# AMini3350.net
KiCad netlist of a schematic drawn in EAGLE
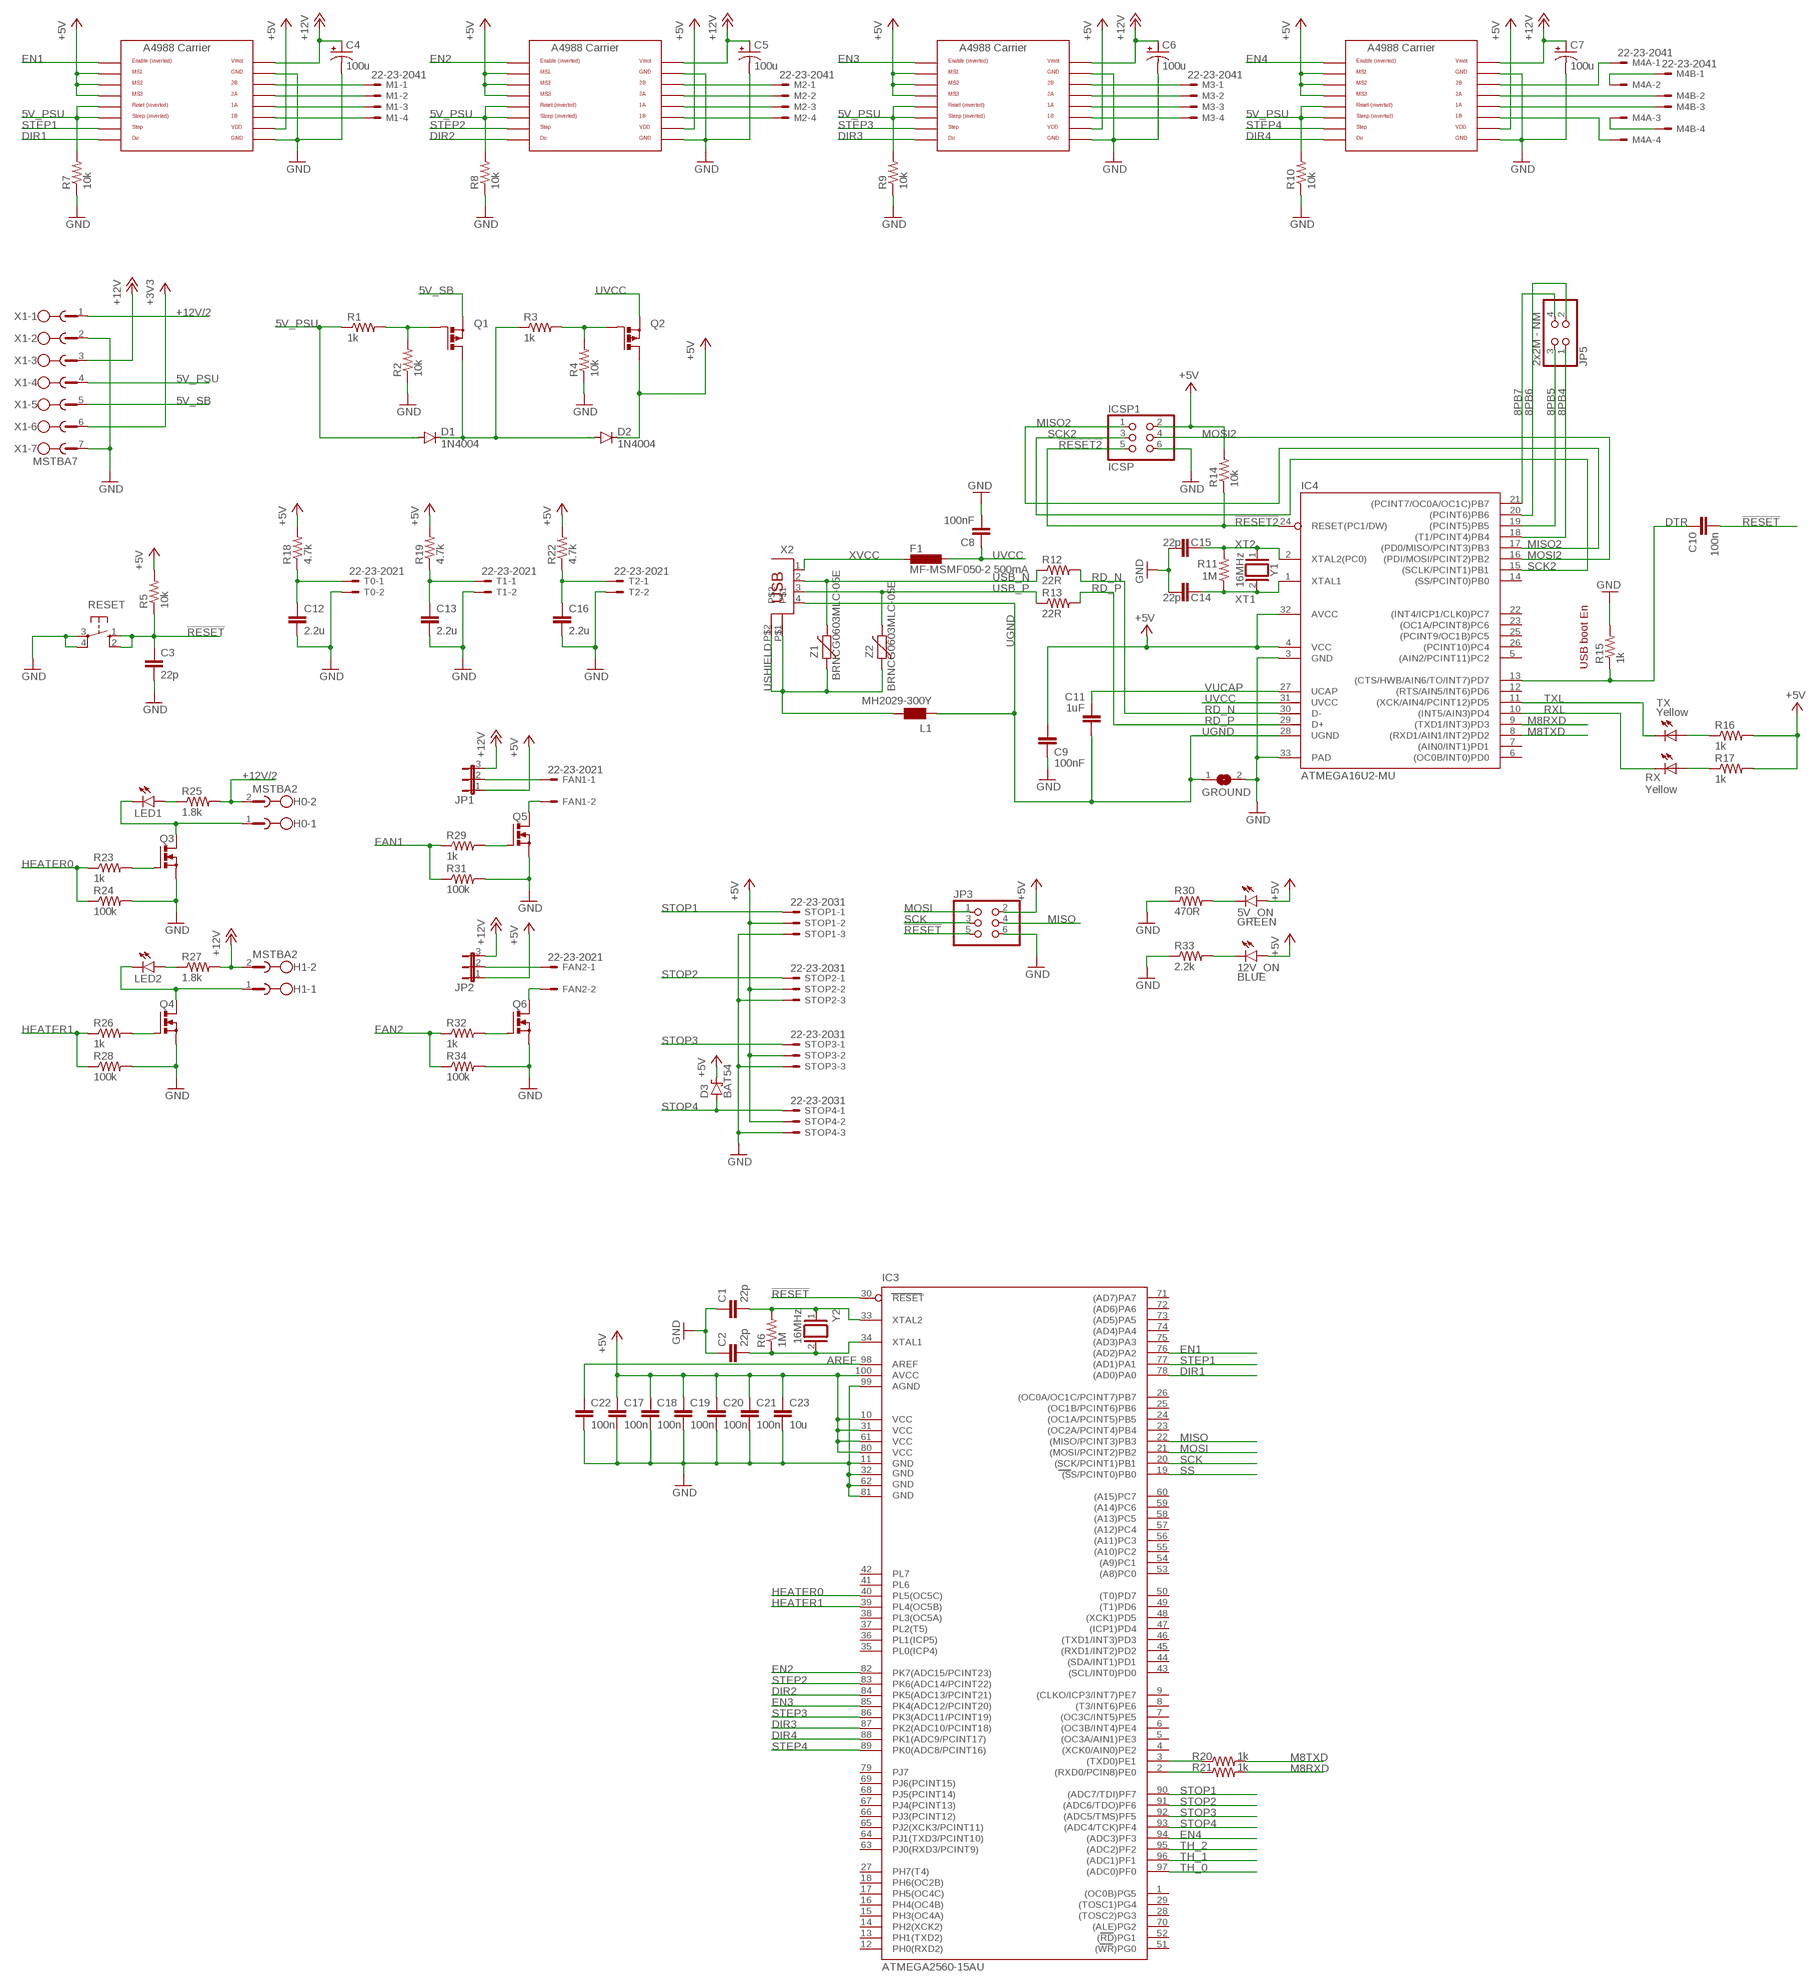
[diagram p0: schematic, sheet 1]

(export (version "E")
  (design (tool "Eeschema 10.0.6"))
  (components
    (comp (ref "5V_ON")
      (value "GREEN")
      (footprint "eagle-import:CHIP-LED0805")
      (libsource (lib "eagle-import") (part "LEDCHIP-LED0805"))
    )
    (comp (ref "12V_ON")
      (value "BLUE")
      (footprint "eagle-import:CHIP-LED0805")
      (libsource (lib "eagle-import") (part "LEDCHIP-LED0805"))
    )
    (comp (ref "C1")
      (value "22p")
      (footprint "eagle-import:C0603")
      (libsource (lib "eagle-import") (part "C-EUC0603"))
    )
    (comp (ref "C2")
      (value "22p")
      (footprint "eagle-import:C0603")
      (libsource (lib "eagle-import") (part "C-EUC0603"))
    )
    (comp (ref "C3")
      (value "22p")
      (footprint "eagle-import:C0603")
      (libsource (lib "eagle-import") (part "C-EUC0603"))
    )
    (comp (ref "C4")
      (value "100u")
      (footprint "eagle-import:PANASONIC_D")
      (libsource (lib "eagle-import") (part "CPOL-USD"))
    )
    (comp (ref "C5")
      (value "100u")
      (footprint "eagle-import:PANASONIC_D")
      (libsource (lib "eagle-import") (part "CPOL-USD"))
    )
    (comp (ref "C6")
      (value "100u")
      (footprint "eagle-import:PANASONIC_D")
      (libsource (lib "eagle-import") (part "CPOL-USD"))
    )
    (comp (ref "C7")
      (value "100u")
      (footprint "eagle-import:PANASONIC_D")
      (libsource (lib "eagle-import") (part "CPOL-USD"))
    )
    (comp (ref "C8")
      (value "100nF")
      (footprint "eagle-import:C0603")
      (libsource (lib "eagle-import") (part "C-EUC0603"))
    )
    (comp (ref "C9")
      (value "100nF")
      (footprint "eagle-import:C0603")
      (libsource (lib "eagle-import") (part "C-EUC0603"))
    )
    (comp (ref "C10")
      (value "100n")
      (footprint "eagle-import:C0603")
      (libsource (lib "eagle-import") (part "C-EUC0603"))
    )
    (comp (ref "C11")
      (value "1uF")
      (footprint "eagle-import:C0603")
      (libsource (lib "eagle-import") (part "C-EUC0603"))
    )
    (comp (ref "C12")
      (value "2.2u")
      (footprint "eagle-import:C0603")
      (libsource (lib "eagle-import") (part "C-EUC0603"))
    )
    (comp (ref "C13")
      (value "2.2u")
      (footprint "eagle-import:C0603")
      (libsource (lib "eagle-import") (part "C-EUC0603"))
    )
    (comp (ref "C14")
      (value "22p")
      (footprint "eagle-import:C0603")
      (libsource (lib "eagle-import") (part "C-EUC0603"))
    )
    (comp (ref "C15")
      (value "22p")
      (footprint "eagle-import:C0603")
      (libsource (lib "eagle-import") (part "C-EUC0603"))
    )
    (comp (ref "C16")
      (value "2.2u")
      (footprint "eagle-import:C0603")
      (libsource (lib "eagle-import") (part "C-EUC0603"))
    )
    (comp (ref "C17")
      (value "100n")
      (footprint "eagle-import:C0603")
      (libsource (lib "eagle-import") (part "C-EUC0603"))
    )
    (comp (ref "C18")
      (value "100n")
      (footprint "eagle-import:C0603")
      (libsource (lib "eagle-import") (part "C-EUC0603"))
    )
    (comp (ref "C19")
      (value "100n")
      (footprint "eagle-import:C0603")
      (libsource (lib "eagle-import") (part "C-EUC0603"))
    )
    (comp (ref "C20")
      (value "100n")
      (footprint "eagle-import:C0603")
      (libsource (lib "eagle-import") (part "C-EUC0603"))
    )
    (comp (ref "C21")
      (value "100n")
      (footprint "eagle-import:C0603")
      (libsource (lib "eagle-import") (part "C-EUC0603"))
    )
    (comp (ref "C22")
      (value "100n")
      (footprint "eagle-import:C0603")
      (libsource (lib "eagle-import") (part "C-EUC0603"))
    )
    (comp (ref "C23")
      (value "10u")
      (footprint "eagle-import:C0805")
      (libsource (lib "eagle-import") (part "C-EUC0805"))
    )
    (comp (ref "D1")
      (value "1N4004")
      (footprint "eagle-import:DO41-10")
      (libsource (lib "eagle-import") (part "1N4004"))
    )
    (comp (ref "D2")
      (value "1N4004")
      (footprint "eagle-import:DO41-10")
      (libsource (lib "eagle-import") (part "1N4004"))
    )
    (comp (ref "D3")
      (value "BAT54")
      (footprint "eagle-import:SOT23")
      (libsource (lib "eagle-import") (part "BAT54"))
    )
    (comp (ref "F1")
      (value "MF-MSMF050-2 500mA")
      (footprint "eagle-import:L1812")
      (fields (field (name "PART_NUMBER") "MF-MSMF050-2"))
      (libsource (lib "eagle-import") (part "0002_MF-MSMF050-2"))
    )
    (comp (ref "FAN1")
      (value "22-23-2021")
      (footprint "eagle-import:22-23-2021")
      (fields (field (name "MF") "MOLEX"))
      (libsource (lib "eagle-import") (part "22-23-2021"))
    )
    (comp (ref "FAN2")
      (value "22-23-2021")
      (footprint "eagle-import:22-23-2021")
      (fields (field (name "MF") "MOLEX"))
      (libsource (lib "eagle-import") (part "22-23-2021"))
    )
    (comp (ref "GROUND")
      (value "SJ")
      (footprint "eagle-import:SJ")
      (libsource (lib "eagle-import") (part "SJ"))
    )
    (comp (ref "H0")
      (value "MSTBA2")
      (footprint "eagle-import:MSTBA2")
      (fields (field (name "MF") "FARNELL") (field (name "MPN") "1757242"))
      (libsource (lib "eagle-import") (part "MSTBA2"))
    )
    (comp (ref "H1")
      (value "MSTBA2")
      (footprint "eagle-import:MSTBA2")
      (fields (field (name "MF") "FARNELL") (field (name "MPN") "1757242"))
      (libsource (lib "eagle-import") (part "MSTBA2"))
    )
    (comp (ref "IC3")
      (value "ATMEGA2560-15AU")
      (footprint "eagle-import:TQFP100")
      (fields (field (name "PART_NUMBER") "ATMEGA2560-16AU"))
      (libsource (lib "eagle-import") (part "0023_ATMEGA2560-16AU"))
    )
    (comp (ref "IC4")
      (value "ATMEGA16U2-MU")
      (footprint "eagle-import:MLF32")
      (fields (field (name "PART_NUMBER") "ATMEGA16U2-MUR"))
      (libsource (lib "eagle-import") (part "0007_ATMEGA16U2-MUR"))
    )
    (comp (ref "ICSP1")
      (value "ICSP")
      (footprint "eagle-import:2X03")
      (fields (field (name "PART_NUMBER") "PH254-203DF118A00V"))
      (libsource (lib "eagle-import") (part "0114_PH254-203DF118A00V"))
    )
    (comp (ref "JP1")
      (value "JP2E")
      (footprint "eagle-import:JP2")
      (libsource (lib "eagle-import") (part "JP2E"))
    )
    (comp (ref "JP2")
      (value "JP2E")
      (footprint "eagle-import:JP2")
      (libsource (lib "eagle-import") (part "JP2E"))
    )
    (comp (ref "JP3")
      (value "PINHD-2X3")
      (footprint "eagle-import:2X03")
      (libsource (lib "eagle-import") (part "PINHD-2X3"))
    )
    (comp (ref "JP5")
      (value "2x2M - NM")
      (footprint "eagle-import:2X02")
      (libsource (lib "eagle-import") (part "PINHD-2X2"))
    )
    (comp (ref "L1")
      (value "MH2029-300Y")
      (footprint "eagle-import:0805")
      (fields (field (name "PART_NUMBER") "BLM21PG300SN1D_/_MH2029-300Y"))
      (libsource (lib "eagle-import") (part "0001_BLM21PG300SN1D_/_MH2029-300Y"))
    )
    (comp (ref "LED1")
      (value "LEDCHIP-LED0805")
      (footprint "eagle-import:CHIP-LED0805")
      (libsource (lib "eagle-import") (part "LEDCHIP-LED0805"))
    )
    (comp (ref "LED2")
      (value "LEDCHIP-LED0805")
      (footprint "eagle-import:CHIP-LED0805")
      (libsource (lib "eagle-import") (part "LEDCHIP-LED0805"))
    )
    (comp (ref "M1")
      (value "22-23-2041")
      (footprint "eagle-import:22-23-2041")
      (fields (field (name "MF") "MOLEX"))
      (libsource (lib "eagle-import") (part "22-23-2041"))
    )
    (comp (ref "M2")
      (value "22-23-2041")
      (footprint "eagle-import:22-23-2041")
      (fields (field (name "MF") "MOLEX"))
      (libsource (lib "eagle-import") (part "22-23-2041"))
    )
    (comp (ref "M3")
      (value "22-23-2041")
      (footprint "eagle-import:22-23-2041")
      (fields (field (name "MF") "MOLEX"))
      (libsource (lib "eagle-import") (part "22-23-2041"))
    )
    (comp (ref "M4A")
      (value "22-23-2041")
      (footprint "eagle-import:22-23-2041")
      (fields (field (name "MF") "MOLEX"))
      (libsource (lib "eagle-import") (part "22-23-2041"))
    )
    (comp (ref "M4B")
      (value "22-23-2041")
      (footprint "eagle-import:22-23-2041")
      (fields (field (name "MF") "MOLEX"))
      (libsource (lib "eagle-import") (part "22-23-2041"))
    )
    (comp (ref "Q1")
      (value "PMOSFET_PTO220BV")
      (footprint "eagle-import:TO220BV")
      (libsource (lib "eagle-import") (part "PMOSFET_PTO220BV"))
    )
    (comp (ref "Q2")
      (value "PMOSFET_PTO220BV")
      (footprint "eagle-import:TO220BV")
      (libsource (lib "eagle-import") (part "PMOSFET_PTO220BV"))
    )
    (comp (ref "Q3")
      (value "PMOSFET_NTO220BV")
      (footprint "eagle-import:TO220BV")
      (libsource (lib "eagle-import") (part "PMOSFET_NTO220BV"))
    )
    (comp (ref "Q4")
      (value "PMOSFET_NTO220BV")
      (footprint "eagle-import:TO220BV")
      (libsource (lib "eagle-import") (part "PMOSFET_NTO220BV"))
    )
    (comp (ref "Q5")
      (value "PMOSFET_NTO220BV")
      (footprint "eagle-import:TO220BV")
      (libsource (lib "eagle-import") (part "PMOSFET_NTO220BV"))
    )
    (comp (ref "Q6")
      (value "PMOSFET_NTO220BV")
      (footprint "eagle-import:TO220BV")
      (libsource (lib "eagle-import") (part "PMOSFET_NTO220BV"))
    )
    (comp (ref "R1")
      (value "1k")
      (footprint "eagle-import:R0603")
      (libsource (lib "eagle-import") (part "R-US_R0603"))
    )
    (comp (ref "R2")
      (value "10k")
      (footprint "eagle-import:R0603")
      (libsource (lib "eagle-import") (part "R-US_R0603"))
    )
    (comp (ref "R3")
      (value "1k")
      (footprint "eagle-import:R0603")
      (libsource (lib "eagle-import") (part "R-US_R0603"))
    )
    (comp (ref "R4")
      (value "10k")
      (footprint "eagle-import:R0603")
      (libsource (lib "eagle-import") (part "R-US_R0603"))
    )
    (comp (ref "R5")
      (value "10k")
      (footprint "eagle-import:R0603")
      (libsource (lib "eagle-import") (part "R-US_R0603"))
    )
    (comp (ref "R6")
      (value "1M")
      (footprint "eagle-import:R0603")
      (libsource (lib "eagle-import") (part "R-US_R0603"))
    )
    (comp (ref "R7")
      (value "10k")
      (footprint "eagle-import:R0603")
      (libsource (lib "eagle-import") (part "R-US_R0603"))
    )
    (comp (ref "R8")
      (value "10k")
      (footprint "eagle-import:R0603")
      (libsource (lib "eagle-import") (part "R-US_R0603"))
    )
    (comp (ref "R9")
      (value "10k")
      (footprint "eagle-import:R0603")
      (libsource (lib "eagle-import") (part "R-US_R0603"))
    )
    (comp (ref "R10")
      (value "10k")
      (footprint "eagle-import:R0603")
      (libsource (lib "eagle-import") (part "R-US_R0603"))
    )
    (comp (ref "R11")
      (value "1M")
      (footprint "eagle-import:R0603")
      (libsource (lib "eagle-import") (part "R-US_R0603"))
    )
    (comp (ref "R12")
      (value "22R")
      (footprint "eagle-import:R0603")
      (libsource (lib "eagle-import") (part "R-US_R0603"))
    )
    (comp (ref "R13")
      (value "22R")
      (footprint "eagle-import:R0603")
      (libsource (lib "eagle-import") (part "R-US_R0603"))
    )
    (comp (ref "R14")
      (value "10k")
      (footprint "eagle-import:R0603")
      (libsource (lib "eagle-import") (part "R-US_R0603"))
    )
    (comp (ref "R15")
      (value "1k")
      (footprint "eagle-import:R0603")
      (libsource (lib "eagle-import") (part "R-US_R0603"))
    )
    (comp (ref "R16")
      (value "1k")
      (footprint "eagle-import:R0603")
      (libsource (lib "eagle-import") (part "R-US_R0603"))
    )
    (comp (ref "R17")
      (value "1k")
      (footprint "eagle-import:R0603")
      (libsource (lib "eagle-import") (part "R-US_R0603"))
    )
    (comp (ref "R18")
      (value "4.7k")
      (footprint "eagle-import:R0603")
      (libsource (lib "eagle-import") (part "R-US_R0603"))
    )
    (comp (ref "R19")
      (value "4.7k")
      (footprint "eagle-import:R0603")
      (libsource (lib "eagle-import") (part "R-US_R0603"))
    )
    (comp (ref "R20")
      (value "1k")
      (footprint "eagle-import:R0603")
      (libsource (lib "eagle-import") (part "R-US_R0603"))
    )
    (comp (ref "R21")
      (value "1k")
      (footprint "eagle-import:R0603")
      (libsource (lib "eagle-import") (part "R-US_R0603"))
    )
    (comp (ref "R22")
      (value "4.7k")
      (footprint "eagle-import:R0603")
      (libsource (lib "eagle-import") (part "R-US_R0603"))
    )
    (comp (ref "R23")
      (value "1k")
      (footprint "eagle-import:R0603")
      (libsource (lib "eagle-import") (part "R-US_R0603"))
    )
    (comp (ref "R24")
      (value "100k")
      (footprint "eagle-import:R0603")
      (libsource (lib "eagle-import") (part "R-US_R0603"))
    )
    (comp (ref "R25")
      (value "1.8k")
      (footprint "eagle-import:R0603")
      (libsource (lib "eagle-import") (part "R-US_R0603"))
    )
    (comp (ref "R26")
      (value "1k")
      (footprint "eagle-import:R0603")
      (libsource (lib "eagle-import") (part "R-US_R0603"))
    )
    (comp (ref "R27")
      (value "1.8k")
      (footprint "eagle-import:R0603")
      (libsource (lib "eagle-import") (part "R-US_R0603"))
    )
    (comp (ref "R28")
      (value "100k")
      (footprint "eagle-import:R0603")
      (libsource (lib "eagle-import") (part "R-US_R0603"))
    )
    (comp (ref "R29")
      (value "1k")
      (footprint "eagle-import:R0603")
      (libsource (lib "eagle-import") (part "R-US_R0603"))
    )
    (comp (ref "R30")
      (value "470R")
      (footprint "eagle-import:R0603")
      (libsource (lib "eagle-import") (part "R-US_R0603"))
    )
    (comp (ref "R31")
      (value "100k")
      (footprint "eagle-import:R0603")
      (libsource (lib "eagle-import") (part "R-US_R0603"))
    )
    (comp (ref "R32")
      (value "1k")
      (footprint "eagle-import:R0603")
      (libsource (lib "eagle-import") (part "R-US_R0603"))
    )
    (comp (ref "R33")
      (value "2.2k")
      (footprint "eagle-import:R0603")
      (libsource (lib "eagle-import") (part "R-US_R0603"))
    )
    (comp (ref "R34")
      (value "100k")
      (footprint "eagle-import:R0603")
      (libsource (lib "eagle-import") (part "R-US_R0603"))
    )
    (comp (ref "RESET")
      (value "10-XX")
      (footprint "eagle-import:B3F-10XX")
      (fields (field (name "MPN") "B3F-1000"))
      (libsource (lib "eagle-import") (part "10-XX"))
    )
    (comp (ref "RX")
      (value "Yellow")
      (footprint "eagle-import:CHIPLED_0805")
      (fields (field (name "PART_NUMBER") "KPT-2012YC"))
      (libsource (lib "eagle-import") (part "0044_KPT-2012YC"))
    )
    (comp (ref "STOP1")
      (value "22-23-2031")
      (footprint "eagle-import:22-23-2031")
      (fields (field (name "MF") "MOLEX"))
      (libsource (lib "eagle-import") (part "22-23-2031"))
    )
    (comp (ref "STOP2")
      (value "22-23-2031")
      (footprint "eagle-import:22-23-2031")
      (fields (field (name "MF") "MOLEX"))
      (libsource (lib "eagle-import") (part "22-23-2031"))
    )
    (comp (ref "STOP3")
      (value "22-23-2031")
      (footprint "eagle-import:22-23-2031")
      (fields (field (name "MF") "MOLEX"))
      (libsource (lib "eagle-import") (part "22-23-2031"))
    )
    (comp (ref "STOP4")
      (value "22-23-2031")
      (footprint "eagle-import:22-23-2031")
      (fields (field (name "MF") "MOLEX"))
      (libsource (lib "eagle-import") (part "22-23-2031"))
    )
    (comp (ref "T0")
      (value "22-23-2021")
      (footprint "eagle-import:22-23-2021")
      (fields (field (name "MF") "MOLEX"))
      (libsource (lib "eagle-import") (part "22-23-2021"))
    )
    (comp (ref "T1")
      (value "22-23-2021")
      (footprint "eagle-import:22-23-2021")
      (fields (field (name "MF") "MOLEX"))
      (libsource (lib "eagle-import") (part "22-23-2021"))
    )
    (comp (ref "T2")
      (value "22-23-2021")
      (footprint "eagle-import:22-23-2021")
      (fields (field (name "MF") "MOLEX"))
      (libsource (lib "eagle-import") (part "22-23-2021"))
    )
    (comp (ref "TX")
      (value "Yellow")
      (footprint "eagle-import:CHIPLED_0805")
      (fields (field (name "PART_NUMBER") "KPT-2012YC"))
      (libsource (lib "eagle-import") (part "0044_KPT-2012YC"))
    )
    (comp (ref "U$1")
      (value "A4988BREAKOUT")
      (footprint "eagle-import:A4988BREAKOUT")
      (libsource (lib "eagle-import") (part "A4988BREAKOUT"))
    )
    (comp (ref "U$2")
      (value "A4988BREAKOUT")
      (footprint "eagle-import:A4988BREAKOUT")
      (libsource (lib "eagle-import") (part "A4988BREAKOUT"))
    )
    (comp (ref "U$3")
      (value "A4988BREAKOUT")
      (footprint "eagle-import:A4988BREAKOUT")
      (libsource (lib "eagle-import") (part "A4988BREAKOUT"))
    )
    (comp (ref "U$4")
      (value "A4988BREAKOUT")
      (footprint "eagle-import:A4988BREAKOUT")
      (libsource (lib "eagle-import") (part "A4988BREAKOUT"))
    )
    (comp (ref "X1")
      (value "MSTBA7")
      (footprint "eagle-import:MSTBA7")
      (libsource (lib "eagle-import") (part "MSTBA7"))
    )
    (comp (ref "X2")
      (value "0056_USB-B-S-RA-WT-SPCC")
      (footprint "eagle-import:PN61729")
      (fields (field (name "PART_NUMBER") "USB-B-S-RA-WT-SPCC"))
      (libsource (lib "eagle-import") (part "0056_USB-B-S-RA-WT-SPCC"))
    )
    (comp (ref "Y1")
      (value "16MHz")
      (footprint "eagle-import:QS")
      (fields (field (name "PART_NUMBER") "P011052006 16M/FTX16M20S"))
      (libsource (lib "eagle-import") (part "0019_P011052006_16M"))
    )
    (comp (ref "Y2")
      (value "16MHz")
      (footprint "eagle-import:QS")
      (fields (field (name "PART_NUMBER") "P011052006 16M/FTX16M20S"))
      (libsource (lib "eagle-import") (part "0019_P011052006_16M"))
    )
    (comp (ref "Z1")
      (value "BRNCG0603MLC-05E")
      (footprint "eagle-import:CT_CN0603")
      (libsource (lib "eagle-import") (part "0010_BRNCG0603MLC-05E"))
    )
    (comp (ref "Z2")
      (value "BRNCG0603MLC-05E")
      (footprint "eagle-import:CT_CN0603")
      (libsource (lib "eagle-import") (part "0010_BRNCG0603MLC-05E"))
    )
  )
  (nets
    (net (code "1") (name "+3V3") (class "Default")
      (node (ref "X1") (pin "6") (pinfunction "1_6") (pintype "passive"))
    )
    (net (code "2") (name "+5V") (class "Default")
      (node (ref "12V_ON") (pin "A") (pinfunction "A_A") (pintype "passive"))
      (node (ref "5V_ON") (pin "A") (pinfunction "A_A") (pintype "passive"))
      (node (ref "C17") (pin "1") (pinfunction "1_1") (pintype "passive"))
      (node (ref "C18") (pin "1") (pinfunction "1_1") (pintype "passive"))
      (node (ref "C19") (pin "1") (pinfunction "1_1") (pintype "passive"))
      (node (ref "C20") (pin "1") (pinfunction "1_1") (pintype "passive"))
      (node (ref "C21") (pin "1") (pinfunction "1_1") (pintype "passive"))
      (node (ref "C23") (pin "1") (pinfunction "1_1") (pintype "passive"))
      (node (ref "C9") (pin "1") (pinfunction "1_1") (pintype "passive"))
      (node (ref "D2") (pin "C") (pinfunction "C_C") (pintype "passive"))
      (node (ref "D3") (pin "3") (pinfunction "C_3") (pintype "passive"))
      (node (ref "IC3") (pin "10") (pinfunction "VCC_10") (pintype "power_in"))
      (node (ref "IC3") (pin "100") (pinfunction "AVCC_100") (pintype "power_in"))
      (node (ref "IC3") (pin "31") (pinfunction "VCC1_31") (pintype "power_in"))
      (node (ref "IC3") (pin "61") (pinfunction "VCC2_61") (pintype "power_in"))
      (node (ref "IC3") (pin "80") (pinfunction "VCC3_80") (pintype "power_in"))
      (node (ref "IC4") (pin "32") (pinfunction "AVCC_32") (pintype "power_in"))
      (node (ref "IC4") (pin "4") (pinfunction "VCC_4") (pintype "power_in"))
      (node (ref "ICSP1") (pin "2") (pinfunction "2_2") (pintype "passive"))
      (node (ref "JP1") (pin "1") (pinfunction "1_1") (pintype "passive"))
      (node (ref "JP2") (pin "1") (pinfunction "1_1") (pintype "passive"))
      (node (ref "JP3") (pin "2") (pinfunction "2_2") (pintype "passive"))
      (node (ref "Q2") (pin "D") (pinfunction "D_D") (pintype "passive"))
      (node (ref "R14") (pin "2") (pinfunction "2_2") (pintype "passive"))
      (node (ref "R16") (pin "2") (pinfunction "2_2") (pintype "passive"))
      (node (ref "R17") (pin "2") (pinfunction "2_2") (pintype "passive"))
      (node (ref "R18") (pin "2") (pinfunction "2_2") (pintype "passive"))
      (node (ref "R19") (pin "2") (pinfunction "2_2") (pintype "passive"))
      (node (ref "R22") (pin "2") (pinfunction "2_2") (pintype "passive"))
      (node (ref "R5") (pin "2") (pinfunction "2_2") (pintype "passive"))
      (node (ref "STOP1") (pin "2") (pinfunction "S_2") (pintype "passive"))
      (node (ref "STOP2") (pin "2") (pinfunction "S_2") (pintype "passive"))
      (node (ref "STOP3") (pin "2") (pinfunction "S_2") (pintype "passive"))
      (node (ref "STOP4") (pin "2") (pinfunction "S_2") (pintype "passive"))
      (node (ref "U$1") (pin "MS1") (pinfunction "MS1_MS1") (pintype "input"))
      (node (ref "U$1") (pin "MS2") (pinfunction "MS2_MS2") (pintype "input"))
      (node (ref "U$1") (pin "MS3") (pinfunction "MS3_MS3") (pintype "input"))
      (node (ref "U$1") (pin "VDD") (pinfunction "VDD_VDD") (pintype "power_in"))
      (node (ref "U$2") (pin "MS1") (pinfunction "MS1_MS1") (pintype "input"))
      (node (ref "U$2") (pin "MS2") (pinfunction "MS2_MS2") (pintype "input"))
      (node (ref "U$2") (pin "MS3") (pinfunction "MS3_MS3") (pintype "input"))
      (node (ref "U$2") (pin "VDD") (pinfunction "VDD_VDD") (pintype "power_in"))
      (node (ref "U$3") (pin "MS1") (pinfunction "MS1_MS1") (pintype "input"))
      (node (ref "U$3") (pin "MS2") (pinfunction "MS2_MS2") (pintype "input"))
      (node (ref "U$3") (pin "MS3") (pinfunction "MS3_MS3") (pintype "input"))
      (node (ref "U$3") (pin "VDD") (pinfunction "VDD_VDD") (pintype "power_in"))
      (node (ref "U$4") (pin "MS1") (pinfunction "MS1_MS1") (pintype "input"))
      (node (ref "U$4") (pin "MS2") (pinfunction "MS2_MS2") (pintype "input"))
      (node (ref "U$4") (pin "MS3") (pinfunction "MS3_MS3") (pintype "input"))
      (node (ref "U$4") (pin "VDD") (pinfunction "VDD_VDD") (pintype "power_in"))
    )
    (net (code "3") (name "+12V") (class "Default")
      (node (ref "C4") (pin "+") (pinfunction "+_+") (pintype "passive"))
      (node (ref "C5") (pin "+") (pinfunction "+_+") (pintype "passive"))
      (node (ref "C6") (pin "+") (pinfunction "+_+") (pintype "passive"))
      (node (ref "C7") (pin "+") (pinfunction "+_+") (pintype "passive"))
      (node (ref "H1") (pin "2") (pinfunction "1_2") (pintype "passive"))
      (node (ref "JP1") (pin "3") (pinfunction "3_3") (pintype "passive"))
      (node (ref "JP2") (pin "3") (pinfunction "3_3") (pintype "passive"))
      (node (ref "R27") (pin "2") (pinfunction "2_2") (pintype "passive"))
      (node (ref "U$1") (pin "VMOT") (pinfunction "VMOT_VMOT") (pintype "power_in"))
      (node (ref "U$2") (pin "VMOT") (pinfunction "VMOT_VMOT") (pintype "power_in"))
      (node (ref "U$3") (pin "VMOT") (pinfunction "VMOT_VMOT") (pintype "power_in"))
      (node (ref "U$4") (pin "VMOT") (pinfunction "VMOT_VMOT") (pintype "power_in"))
      (node (ref "X1") (pin "3") (pinfunction "1_3") (pintype "passive"))
    )
    (net (code "4") (name "/+12V{slash}2") (class "Default")
      (node (ref "H0") (pin "2") (pinfunction "1_2") (pintype "passive"))
      (node (ref "R25") (pin "2") (pinfunction "2_2") (pintype "passive"))
      (node (ref "X1") (pin "1") (pinfunction "1_1") (pintype "passive"))
    )
    (net (code "5") (name "/5V_PSU") (class "Default")
      (node (ref "D1") (pin "A") (pinfunction "A_A") (pintype "passive"))
      (node (ref "R1") (pin "1") (pinfunction "1_1") (pintype "passive"))
      (node (ref "R10") (pin "2") (pinfunction "2_2") (pintype "passive"))
      (node (ref "R7") (pin "2") (pinfunction "2_2") (pintype "passive"))
      (node (ref "R8") (pin "2") (pinfunction "2_2") (pintype "passive"))
      (node (ref "R9") (pin "2") (pinfunction "2_2") (pintype "passive"))
      (node (ref "U$1") (pin "RST") (pinfunction "RST_RST") (pintype "input"))
      (node (ref "U$1") (pin "SLP") (pinfunction "SLEEP_SLP") (pintype "input"))
      (node (ref "U$2") (pin "RST") (pinfunction "RST_RST") (pintype "input"))
      (node (ref "U$2") (pin "SLP") (pinfunction "SLEEP_SLP") (pintype "input"))
      (node (ref "U$3") (pin "RST") (pinfunction "RST_RST") (pintype "input"))
      (node (ref "U$3") (pin "SLP") (pinfunction "SLEEP_SLP") (pintype "input"))
      (node (ref "U$4") (pin "RST") (pinfunction "RST_RST") (pintype "input"))
      (node (ref "U$4") (pin "SLP") (pinfunction "SLEEP_SLP") (pintype "input"))
      (node (ref "X1") (pin "4") (pinfunction "1_4") (pintype "passive"))
    )
    (net (code "6") (name "/5V_SB") (class "Default")
      (node (ref "Q1") (pin "S") (pinfunction "S_S") (pintype "passive"))
      (node (ref "X1") (pin "5") (pinfunction "1_5") (pintype "passive"))
    )
    (net (code "7") (name "/8PB4") (class "Default")
      (node (ref "IC4") (pin "18") (pinfunction "(T1/PCINT4)PB4_18") (pintype "bidirectional"))
      (node (ref "JP5") (pin "1") (pinfunction "1_1") (pintype "passive"))
    )
    (net (code "8") (name "/8PB5") (class "Default")
      (node (ref "IC4") (pin "19") (pinfunction "(PCINT5)PB5_19") (pintype "bidirectional"))
      (node (ref "JP5") (pin "3") (pinfunction "3_3") (pintype "passive"))
    )
    (net (code "9") (name "/8PB6") (class "Default")
      (node (ref "IC4") (pin "20") (pinfunction "(PCINT6)PB6_20") (pintype "bidirectional"))
      (node (ref "JP5") (pin "2") (pinfunction "2_2") (pintype "passive"))
    )
    (net (code "10") (name "/8PB7") (class "Default")
      (node (ref "IC4") (pin "21") (pinfunction "(PCINT7/OC0A/OC1C)PB7_21") (pintype "bidirectional"))
      (node (ref "JP5") (pin "4") (pinfunction "4_4") (pintype "passive"))
    )
    (net (code "11") (name "/AREF") (class "Default")
      (node (ref "C22") (pin "1") (pinfunction "1_1") (pintype "passive"))
      (node (ref "IC3") (pin "98") (pinfunction "AREF_98") (pintype "bidirectional"))
    )
    (net (code "12") (name "/DIR1") (class "Default")
      (node (ref "IC3") (pin "78") (pinfunction "(AD0)PA0_78") (pintype "bidirectional"))
      (node (ref "U$1") (pin "DIR") (pinfunction "DIR_DIR") (pintype "input"))
    )
    (net (code "13") (name "/DIR2") (class "Default")
      (node (ref "IC3") (pin "84") (pinfunction "PK5(ADC13/PCINT21)_84") (pintype "bidirectional"))
      (node (ref "U$2") (pin "DIR") (pinfunction "DIR_DIR") (pintype "input"))
    )
    (net (code "14") (name "/DIR3") (class "Default")
      (node (ref "IC3") (pin "87") (pinfunction "PK2(ADC10/PCINT18)_87") (pintype "bidirectional"))
      (node (ref "U$3") (pin "DIR") (pinfunction "DIR_DIR") (pintype "input"))
    )
    (net (code "15") (name "/DIR4") (class "Default")
      (node (ref "IC3") (pin "88") (pinfunction "PK1(ADC9/PCINT17)_88") (pintype "bidirectional"))
      (node (ref "U$4") (pin "DIR") (pinfunction "DIR_DIR") (pintype "input"))
    )
    (net (code "16") (name "/DTR") (class "Default")
      (node (ref "C10") (pin "1") (pinfunction "1_1") (pintype "passive"))
      (node (ref "IC4") (pin "13") (pinfunction "(CTS/HWB/AIN6/TO/INT7)PD7_13") (pintype "bidirectional"))
      (node (ref "R15") (pin "1") (pinfunction "1_1") (pintype "passive"))
    )
    (net (code "17") (name "/EN1") (class "Default")
      (node (ref "IC3") (pin "76") (pinfunction "(AD2)PA2_76") (pintype "bidirectional"))
      (node (ref "U$1") (pin "EN") (pinfunction "EN_EN") (pintype "input"))
    )
    (net (code "18") (name "/EN2") (class "Default")
      (node (ref "IC3") (pin "82") (pinfunction "PK7(ADC15/PCINT23)_82") (pintype "bidirectional"))
      (node (ref "U$2") (pin "EN") (pinfunction "EN_EN") (pintype "input"))
    )
    (net (code "19") (name "/EN3") (class "Default")
      (node (ref "IC3") (pin "85") (pinfunction "PK4(ADC12/PCINT20)_85") (pintype "bidirectional"))
      (node (ref "U$3") (pin "EN") (pinfunction "EN_EN") (pintype "input"))
    )
    (net (code "20") (name "/EN4") (class "Default")
      (node (ref "IC3") (pin "94") (pinfunction "(ADC3)PF3_94") (pintype "bidirectional"))
      (node (ref "U$4") (pin "EN") (pinfunction "EN_EN") (pintype "input"))
    )
    (net (code "21") (name "/FAN1") (class "Default")
      (node (ref "R29") (pin "1") (pinfunction "1_1") (pintype "passive"))
      (node (ref "R31") (pin "1") (pinfunction "1_1") (pintype "passive"))
    )
    (net (code "22") (name "/FAN2") (class "Default")
      (node (ref "R32") (pin "1") (pinfunction "1_1") (pintype "passive"))
      (node (ref "R34") (pin "1") (pinfunction "1_1") (pintype "passive"))
    )
    (net (code "23") (name "/HEATER0") (class "Default")
      (node (ref "IC3") (pin "40") (pinfunction "PL5(OC5C)_40") (pintype "bidirectional"))
      (node (ref "R23") (pin "1") (pinfunction "1_1") (pintype "passive"))
      (node (ref "R24") (pin "1") (pinfunction "1_1") (pintype "passive"))
    )
    (net (code "24") (name "/HEATER1") (class "Default")
      (node (ref "IC3") (pin "39") (pinfunction "PL4(OC5B)_39") (pintype "bidirectional"))
      (node (ref "R26") (pin "1") (pinfunction "1_1") (pintype "passive"))
      (node (ref "R28") (pin "1") (pinfunction "1_1") (pintype "passive"))
    )
    (net (code "25") (name "/M8RXD") (class "Default")
      (node (ref "IC4") (pin "9") (pinfunction "(TXD1/INT3)PD3_9") (pintype "bidirectional"))
      (node (ref "R21") (pin "2") (pinfunction "2_2") (pintype "passive"))
    )
    (net (code "26") (name "/M8TXD") (class "Default")
      (node (ref "IC4") (pin "8") (pinfunction "(RXD1/AIN1/INT2)PD2_8") (pintype "bidirectional"))
      (node (ref "R20") (pin "2") (pinfunction "2_2") (pintype "passive"))
    )
    (net (code "27") (name "/MISO") (class "Default")
      (node (ref "IC3") (pin "22") (pinfunction "(MISO/PCINT3)PB3_22") (pintype "bidirectional"))
      (node (ref "JP3") (pin "4") (pinfunction "4_4") (pintype "passive"))
    )
    (net (code "28") (name "/MISO2") (class "Default")
      (node (ref "IC4") (pin "17") (pinfunction "(PD0/MISO/PCINT3)PB3_17") (pintype "bidirectional"))
      (node (ref "ICSP1") (pin "1") (pinfunction "1_1") (pintype "passive"))
    )
    (net (code "29") (name "/MOSI") (class "Default")
      (node (ref "IC3") (pin "21") (pinfunction "(MOSI/PCINT2)PB2_21") (pintype "bidirectional"))
      (node (ref "JP3") (pin "1") (pinfunction "1_1") (pintype "passive"))
    )
    (net (code "30") (name "/MOSI2") (class "Default")
      (node (ref "IC4") (pin "16") (pinfunction "(PDI/MOSI/PCINT2)PB2_16") (pintype "bidirectional"))
      (node (ref "ICSP1") (pin "4") (pinfunction "4_4") (pintype "passive"))
    )
    (net (code "31") (name "/RD_N") (class "Default")
      (node (ref "IC4") (pin "30") (pinfunction "D-_30") (pintype "bidirectional"))
      (node (ref "R12") (pin "2") (pinfunction "2_2") (pintype "passive"))
    )
    (net (code "32") (name "/RD_P") (class "Default")
      (node (ref "IC4") (pin "29") (pinfunction "D+_29") (pintype "bidirectional"))
      (node (ref "R13") (pin "2") (pinfunction "2_2") (pintype "passive"))
    )
    (net (code "33") (name "/RXL") (class "Default")
      (node (ref "IC4") (pin "10") (pinfunction "(INT5/AIN3)PD4_10") (pintype "bidirectional"))
      (node (ref "RX") (pin "C") (pinfunction "C_C") (pintype "passive"))
    )
    (net (code "34") (name "/SCK") (class "Default")
      (node (ref "IC3") (pin "20") (pinfunction "(SCK/PCINT1)PB1_20") (pintype "bidirectional"))
      (node (ref "JP3") (pin "3") (pinfunction "3_3") (pintype "passive"))
    )
    (net (code "35") (name "/SCK2") (class "Default")
      (node (ref "IC4") (pin "15") (pinfunction "(SCLK/PCINT1)PB1_15") (pintype "bidirectional"))
      (node (ref "ICSP1") (pin "3") (pinfunction "3_3") (pintype "passive"))
    )
    (net (code "36") (name "/SS") (class "Default")
      (node (ref "IC3") (pin "19") (pinfunction "(SS/PCINT0)PB0_19") (pintype "bidirectional"))
    )
    (net (code "37") (name "/STEP1") (class "Default")
      (node (ref "IC3") (pin "77") (pinfunction "(AD1)PA1_77") (pintype "bidirectional"))
      (node (ref "U$1") (pin "STEP") (pinfunction "STEP_STEP") (pintype "input"))
    )
    (net (code "38") (name "/STEP2") (class "Default")
      (node (ref "IC3") (pin "83") (pinfunction "PK6(ADC14/PCINT22)_83") (pintype "bidirectional"))
      (node (ref "U$2") (pin "STEP") (pinfunction "STEP_STEP") (pintype "input"))
    )
    (net (code "39") (name "/STEP3") (class "Default")
      (node (ref "IC3") (pin "86") (pinfunction "PK3(ADC11/PCINT19)_86") (pintype "bidirectional"))
      (node (ref "U$3") (pin "STEP") (pinfunction "STEP_STEP") (pintype "input"))
    )
    (net (code "40") (name "/STEP4") (class "Default")
      (node (ref "IC3") (pin "89") (pinfunction "PK0(ADC8/PCINT16)_89") (pintype "bidirectional"))
      (node (ref "U$4") (pin "STEP") (pinfunction "STEP_STEP") (pintype "input"))
    )
    (net (code "41") (name "/STOP1") (class "Default")
      (node (ref "IC3") (pin "90") (pinfunction "(ADC7/TDI)PF7_90") (pintype "bidirectional"))
      (node (ref "STOP1") (pin "1") (pinfunction "S_1") (pintype "passive"))
    )
    (net (code "42") (name "/STOP2") (class "Default")
      (node (ref "IC3") (pin "91") (pinfunction "(ADC6/TDO)PF6_91") (pintype "bidirectional"))
      (node (ref "STOP2") (pin "1") (pinfunction "S_1") (pintype "passive"))
    )
    (net (code "43") (name "/STOP3") (class "Default")
      (node (ref "IC3") (pin "92") (pinfunction "(ADC5/TMS)PF5_92") (pintype "bidirectional"))
      (node (ref "STOP3") (pin "1") (pinfunction "S_1") (pintype "passive"))
    )
    (net (code "44") (name "/STOP4") (class "Default")
      (node (ref "D3") (pin "1") (pinfunction "A_1") (pintype "passive"))
      (node (ref "IC3") (pin "93") (pinfunction "(ADC4/TCK)PF4_93") (pintype "bidirectional"))
      (node (ref "STOP4") (pin "1") (pinfunction "S_1") (pintype "passive"))
    )
    (net (code "45") (name "/TH_0") (class "Default")
      (node (ref "C12") (pin "1") (pinfunction "1_1") (pintype "passive"))
      (node (ref "IC3") (pin "97") (pinfunction "(ADC0)PF0_97") (pintype "bidirectional"))
      (node (ref "R18") (pin "1") (pinfunction "1_1") (pintype "passive"))
      (node (ref "T0") (pin "1") (pinfunction "S_1") (pintype "passive"))
    )
    (net (code "46") (name "/TH_1") (class "Default")
      (node (ref "C13") (pin "1") (pinfunction "1_1") (pintype "passive"))
      (node (ref "IC3") (pin "96") (pinfunction "(ADC1)PF1_96") (pintype "bidirectional"))
      (node (ref "R19") (pin "1") (pinfunction "1_1") (pintype "passive"))
      (node (ref "T1") (pin "1") (pinfunction "S_1") (pintype "passive"))
    )
    (net (code "47") (name "/TH_2") (class "Default")
      (node (ref "C16") (pin "1") (pinfunction "1_1") (pintype "passive"))
      (node (ref "IC3") (pin "95") (pinfunction "(ADC2)PF2_95") (pintype "bidirectional"))
      (node (ref "R22") (pin "1") (pinfunction "1_1") (pintype "passive"))
      (node (ref "T2") (pin "1") (pinfunction "S_1") (pintype "passive"))
    )
    (net (code "48") (name "/TXL") (class "Default")
      (node (ref "IC4") (pin "11") (pinfunction "(XCK/AIN4/PCINT12)PD5_11") (pintype "bidirectional"))
      (node (ref "TX") (pin "C") (pinfunction "C_C") (pintype "passive"))
    )
    (net (code "49") (name "/UGND") (class "Default")
      (node (ref "C11") (pin "2") (pinfunction "2_2") (pintype "passive"))
      (node (ref "GROUND") (pin "1") (pinfunction "1_1") (pintype "passive"))
      (node (ref "IC4") (pin "28") (pinfunction "UGND_28") (pintype "power_in"))
      (node (ref "L1") (pin "1") (pinfunction "1_1") (pintype "passive"))
      (node (ref "X2") (pin "4") (pinfunction "4_4") (pintype "bidirectional"))
    )
    (net (code "50") (name "/USB_N") (class "Default")
      (node (ref "R12") (pin "1") (pinfunction "1_1") (pintype "passive"))
      (node (ref "X2") (pin "2") (pinfunction "2_2") (pintype "bidirectional"))
      (node (ref "Z1") (pin "2") (pinfunction "2_2") (pintype "passive"))
    )
    (net (code "51") (name "/USB_P") (class "Default")
      (node (ref "R13") (pin "1") (pinfunction "1_1") (pintype "passive"))
      (node (ref "X2") (pin "3") (pinfunction "3_3") (pintype "bidirectional"))
      (node (ref "Z2") (pin "2") (pinfunction "2_2") (pintype "passive"))
    )
    (net (code "52") (name "/USHIELD") (class "Default")
      (node (ref "L1") (pin "2") (pinfunction "2_2") (pintype "passive"))
      (node (ref "X2") (pin "P$1") (pinfunction "P$1_P$1") (pintype "bidirectional"))
      (node (ref "X2") (pin "P$2") (pinfunction "P$2_P$2") (pintype "bidirectional"))
      (node (ref "Z1") (pin "1") (pinfunction "1_1") (pintype "passive"))
      (node (ref "Z2") (pin "1") (pinfunction "1_1") (pintype "passive"))
    )
    (net (code "53") (name "/UVCC") (class "Default")
      (node (ref "C8") (pin "1") (pinfunction "1_1") (pintype "passive"))
      (node (ref "F1") (pin "1") (pinfunction "1_1") (pintype "passive"))
      (node (ref "IC4") (pin "31") (pinfunction "UVCC_31") (pintype "power_in"))
      (node (ref "Q2") (pin "S") (pinfunction "S_S") (pintype "passive"))
    )
    (net (code "54") (name "/VUCAP") (class "Default")
      (node (ref "C11") (pin "1") (pinfunction "1_1") (pintype "passive"))
      (node (ref "IC4") (pin "27") (pinfunction "UCAP_27") (pintype "passive"))
    )
    (net (code "55") (name "/XT1") (class "Default")
      (node (ref "C14") (pin "1") (pinfunction "1_1") (pintype "passive"))
      (node (ref "IC4") (pin "1") (pinfunction "XTAL1_1") (pintype "bidirectional"))
      (node (ref "R11") (pin "1") (pinfunction "1_1") (pintype "passive"))
      (node (ref "Y1") (pin "2") (pinfunction "2_2") (pintype "passive"))
    )
    (net (code "56") (name "/XT2") (class "Default")
      (node (ref "C15") (pin "1") (pinfunction "1_1") (pintype "passive"))
      (node (ref "IC4") (pin "2") (pinfunction "XTAL2(PC0)_2") (pintype "bidirectional"))
      (node (ref "R11") (pin "2") (pinfunction "2_2") (pintype "passive"))
      (node (ref "Y1") (pin "1") (pinfunction "1_1") (pintype "passive"))
    )
    (net (code "57") (name "/XVCC") (class "Default")
      (node (ref "F1") (pin "2") (pinfunction "2_2") (pintype "passive"))
      (node (ref "X2") (pin "1") (pinfunction "1_1") (pintype "bidirectional"))
    )
    (net (code "58") (name "/~{RESET2}") (class "Default")
      (node (ref "IC4") (pin "24") (pinfunction "RESET(PC1/DW)_24") (pintype "input"))
      (node (ref "ICSP1") (pin "5") (pinfunction "5_5") (pintype "passive"))
      (node (ref "R14") (pin "1") (pinfunction "1_1") (pintype "passive"))
    )
    (net (code "59") (name "/~{RESET}") (class "Default")
      (node (ref "C10") (pin "2") (pinfunction "2_2") (pintype "passive"))
      (node (ref "C3") (pin "1") (pinfunction "1_1") (pintype "passive"))
      (node (ref "IC3") (pin "30") (pinfunction "RESET_30") (pintype "input"))
      (node (ref "JP3") (pin "5") (pinfunction "5_5") (pintype "passive"))
      (node (ref "R5") (pin "1") (pinfunction "1_1") (pintype "passive"))
      (node (ref "RESET") (pin "1") (pinfunction "S_1") (pintype "passive"))
      (node (ref "RESET") (pin "2") (pinfunction "S1_2") (pintype "passive"))
    )
    (net (code "60") (name "GND") (class "Default")
      (node (ref "C1") (pin "1") (pinfunction "1_1") (pintype "passive"))
      (node (ref "C12") (pin "2") (pinfunction "2_2") (pintype "passive"))
      (node (ref "C13") (pin "2") (pinfunction "2_2") (pintype "passive"))
      (node (ref "C14") (pin "2") (pinfunction "2_2") (pintype "passive"))
      (node (ref "C15") (pin "2") (pinfunction "2_2") (pintype "passive"))
      (node (ref "C16") (pin "2") (pinfunction "2_2") (pintype "passive"))
      (node (ref "C17") (pin "2") (pinfunction "2_2") (pintype "passive"))
      (node (ref "C18") (pin "2") (pinfunction "2_2") (pintype "passive"))
      (node (ref "C19") (pin "2") (pinfunction "2_2") (pintype "passive"))
      (node (ref "C2") (pin "1") (pinfunction "1_1") (pintype "passive"))
      (node (ref "C20") (pin "2") (pinfunction "2_2") (pintype "passive"))
      (node (ref "C21") (pin "2") (pinfunction "2_2") (pintype "passive"))
      (node (ref "C22") (pin "2") (pinfunction "2_2") (pintype "passive"))
      (node (ref "C23") (pin "2") (pinfunction "2_2") (pintype "passive"))
      (node (ref "C3") (pin "2") (pinfunction "2_2") (pintype "passive"))
      (node (ref "C4") (pin "-") (pinfunction "-_-") (pintype "passive"))
      (node (ref "C5") (pin "-") (pinfunction "-_-") (pintype "passive"))
      (node (ref "C6") (pin "-") (pinfunction "-_-") (pintype "passive"))
      (node (ref "C7") (pin "-") (pinfunction "-_-") (pintype "passive"))
      (node (ref "C8") (pin "2") (pinfunction "2_2") (pintype "passive"))
      (node (ref "C9") (pin "2") (pinfunction "2_2") (pintype "passive"))
      (node (ref "GROUND") (pin "2") (pinfunction "2_2") (pintype "passive"))
      (node (ref "IC3") (pin "11") (pinfunction "GND_11") (pintype "power_in"))
      (node (ref "IC3") (pin "32") (pinfunction "GND1_32") (pintype "power_in"))
      (node (ref "IC3") (pin "62") (pinfunction "GND2_62") (pintype "power_in"))
      (node (ref "IC3") (pin "81") (pinfunction "GND3_81") (pintype "power_in"))
      (node (ref "IC3") (pin "99") (pinfunction "AGND_99") (pintype "power_in"))
      (node (ref "IC4") (pin "3") (pinfunction "GND_3") (pintype "power_in"))
      (node (ref "IC4") (pin "33") (pinfunction "PAD_33") (pintype "power_in"))
      (node (ref "ICSP1") (pin "6") (pinfunction "6_6") (pintype "passive"))
      (node (ref "JP3") (pin "6") (pinfunction "6_6") (pintype "passive"))
      (node (ref "Q3") (pin "S") (pinfunction "S_S") (pintype "passive"))
      (node (ref "Q4") (pin "S") (pinfunction "S_S") (pintype "passive"))
      (node (ref "Q5") (pin "S") (pinfunction "S_S") (pintype "passive"))
      (node (ref "Q6") (pin "S") (pinfunction "S_S") (pintype "passive"))
      (node (ref "R10") (pin "1") (pinfunction "1_1") (pintype "passive"))
      (node (ref "R15") (pin "2") (pinfunction "2_2") (pintype "passive"))
      (node (ref "R2") (pin "1") (pinfunction "1_1") (pintype "passive"))
      (node (ref "R24") (pin "2") (pinfunction "2_2") (pintype "passive"))
      (node (ref "R28") (pin "2") (pinfunction "2_2") (pintype "passive"))
      (node (ref "R30") (pin "1") (pinfunction "1_1") (pintype "passive"))
      (node (ref "R31") (pin "2") (pinfunction "2_2") (pintype "passive"))
      (node (ref "R33") (pin "1") (pinfunction "1_1") (pintype "passive"))
      (node (ref "R34") (pin "2") (pinfunction "2_2") (pintype "passive"))
      (node (ref "R4") (pin "1") (pinfunction "1_1") (pintype "passive"))
      (node (ref "R7") (pin "1") (pinfunction "1_1") (pintype "passive"))
      (node (ref "R8") (pin "1") (pinfunction "1_1") (pintype "passive"))
      (node (ref "R9") (pin "1") (pinfunction "1_1") (pintype "passive"))
      (node (ref "RESET") (pin "3") (pinfunction "P_3") (pintype "passive"))
      (node (ref "RESET") (pin "4") (pinfunction "P1_4") (pintype "passive"))
      (node (ref "STOP1") (pin "3") (pinfunction "S_3") (pintype "passive"))
      (node (ref "STOP2") (pin "3") (pinfunction "S_3") (pintype "passive"))
      (node (ref "STOP3") (pin "3") (pinfunction "S_3") (pintype "passive"))
      (node (ref "STOP4") (pin "3") (pinfunction "S_3") (pintype "passive"))
      (node (ref "T0") (pin "2") (pinfunction "S_2") (pintype "passive"))
      (node (ref "T1") (pin "2") (pinfunction "S_2") (pintype "passive"))
      (node (ref "T2") (pin "2") (pinfunction "S_2") (pintype "passive"))
      (node (ref "U$1") (pin "GND") (pinfunction "GND_GND") (pintype "power_in"))
      (node (ref "U$1") (pin "GND@0") (pinfunction "GND_GND@0") (pintype "power_in"))
      (node (ref "U$2") (pin "GND") (pinfunction "GND_GND") (pintype "power_in"))
      (node (ref "U$2") (pin "GND@0") (pinfunction "GND_GND@0") (pintype "power_in"))
      (node (ref "U$3") (pin "GND") (pinfunction "GND_GND") (pintype "power_in"))
      (node (ref "U$3") (pin "GND@0") (pinfunction "GND_GND@0") (pintype "power_in"))
      (node (ref "U$4") (pin "GND") (pinfunction "GND_GND") (pintype "power_in"))
      (node (ref "U$4") (pin "GND@0") (pinfunction "GND_GND@0") (pintype "power_in"))
      (node (ref "X1") (pin "2") (pinfunction "1_2") (pintype "passive"))
      (node (ref "X1") (pin "7") (pinfunction "1_7") (pintype "passive"))
    )
    (net (code "61") (name "Net-(5V_ON-PadC)") (class "Default")
      (node (ref "5V_ON") (pin "C") (pinfunction "C_C") (pintype "passive"))
      (node (ref "R30") (pin "2") (pinfunction "2_2") (pintype "passive"))
    )
    (net (code "62") (name "Net-(12V_ON-PadC)") (class "Default")
      (node (ref "12V_ON") (pin "C") (pinfunction "C_C") (pintype "passive"))
      (node (ref "R33") (pin "2") (pinfunction "2_2") (pintype "passive"))
    )
    (net (code "63") (name "Net-(D1-PadC)") (class "Default")
      (node (ref "D1") (pin "C") (pinfunction "C_C") (pintype "passive"))
      (node (ref "D2") (pin "A") (pinfunction "A_A") (pintype "passive"))
      (node (ref "Q1") (pin "D") (pinfunction "D_D") (pintype "passive"))
      (node (ref "R3") (pin "1") (pinfunction "1_1") (pintype "passive"))
    )
    (net (code "64") (name "Net-(FAN1A-S)") (class "Default")
      (node (ref "FAN1") (pin "1") (pinfunction "S_1") (pintype "passive"))
      (node (ref "JP1") (pin "2") (pinfunction "2_2") (pintype "passive"))
    )
    (net (code "65") (name "Net-(FAN1B-S)") (class "Default")
      (node (ref "FAN1") (pin "2") (pinfunction "S_2") (pintype "passive"))
      (node (ref "Q5") (pin "D") (pinfunction "D_D") (pintype "passive"))
    )
    (net (code "66") (name "Net-(FAN2A-S)") (class "Default")
      (node (ref "FAN2") (pin "1") (pinfunction "S_1") (pintype "passive"))
      (node (ref "JP2") (pin "2") (pinfunction "2_2") (pintype "passive"))
    )
    (net (code "67") (name "Net-(FAN2B-S)") (class "Default")
      (node (ref "FAN2") (pin "2") (pinfunction "S_2") (pintype "passive"))
      (node (ref "Q6") (pin "D") (pinfunction "D_D") (pintype "passive"))
    )
    (net (code "68") (name "Net-(H0-Pad1)") (class "Default")
      (node (ref "H0") (pin "1") (pinfunction "1_1") (pintype "passive"))
      (node (ref "LED1") (pin "C") (pinfunction "C_C") (pintype "passive"))
      (node (ref "Q3") (pin "D") (pinfunction "D_D") (pintype "passive"))
    )
    (net (code "69") (name "Net-(H1-Pad1)") (class "Default")
      (node (ref "H1") (pin "1") (pinfunction "1_1") (pintype "passive"))
      (node (ref "LED2") (pin "C") (pinfunction "C_C") (pintype "passive"))
      (node (ref "Q4") (pin "D") (pinfunction "D_D") (pintype "passive"))
    )
    (net (code "70") (name "Net-(IC3-(RXD0{slash}PCIN8)PE0)") (class "Default")
      (node (ref "IC3") (pin "2") (pinfunction "(RXD0/PCIN8)PE0_2") (pintype "bidirectional"))
      (node (ref "R21") (pin "1") (pinfunction "1_1") (pintype "passive"))
    )
    (net (code "71") (name "Net-(IC3-(TXD0)PE1)") (class "Default")
      (node (ref "IC3") (pin "3") (pinfunction "(TXD0)PE1_3") (pintype "bidirectional"))
      (node (ref "R20") (pin "1") (pinfunction "1_1") (pintype "passive"))
    )
    (net (code "72") (name "Net-(IC3-XTAL1)") (class "Default")
      (node (ref "C2") (pin "2") (pinfunction "2_2") (pintype "passive"))
      (node (ref "IC3") (pin "34") (pinfunction "XTAL1_34") (pintype "input"))
      (node (ref "R6") (pin "1") (pinfunction "1_1") (pintype "passive"))
      (node (ref "Y2") (pin "2") (pinfunction "2_2") (pintype "passive"))
    )
    (net (code "73") (name "Net-(IC3-XTAL2)") (class "Default")
      (node (ref "C1") (pin "2") (pinfunction "2_2") (pintype "passive"))
      (node (ref "IC3") (pin "33") (pinfunction "XTAL2_33") (pintype "output"))
      (node (ref "R6") (pin "2") (pinfunction "2_2") (pintype "passive"))
      (node (ref "Y2") (pin "1") (pinfunction "1_1") (pintype "passive"))
    )
    (net (code "74") (name "Net-(LED1-PadA)") (class "Default")
      (node (ref "LED1") (pin "A") (pinfunction "A_A") (pintype "passive"))
      (node (ref "R25") (pin "1") (pinfunction "1_1") (pintype "passive"))
    )
    (net (code "75") (name "Net-(LED2-PadA)") (class "Default")
      (node (ref "LED2") (pin "A") (pinfunction "A_A") (pintype "passive"))
      (node (ref "R27") (pin "1") (pinfunction "1_1") (pintype "passive"))
    )
    (net (code "76") (name "Net-(M1A-S)") (class "Default")
      (node (ref "M1") (pin "1") (pinfunction "S_1") (pintype "passive"))
      (node (ref "U$1") (pin "2B") (pinfunction "2B_2B") (pintype "output"))
    )
    (net (code "77") (name "Net-(M1B-S)") (class "Default")
      (node (ref "M1") (pin "2") (pinfunction "S_2") (pintype "passive"))
      (node (ref "U$1") (pin "2A") (pinfunction "2A_2A") (pintype "output"))
    )
    (net (code "78") (name "Net-(M1C-S)") (class "Default")
      (node (ref "M1") (pin "3") (pinfunction "S_3") (pintype "passive"))
      (node (ref "U$1") (pin "1A") (pinfunction "1A_1A") (pintype "output"))
    )
    (net (code "79") (name "Net-(M1D-S)") (class "Default")
      (node (ref "M1") (pin "4") (pinfunction "S_4") (pintype "passive"))
      (node (ref "U$1") (pin "1B") (pinfunction "1B_1B") (pintype "output"))
    )
    (net (code "80") (name "Net-(M2A-S)") (class "Default")
      (node (ref "M2") (pin "1") (pinfunction "S_1") (pintype "passive"))
      (node (ref "U$2") (pin "2B") (pinfunction "2B_2B") (pintype "output"))
    )
    (net (code "81") (name "Net-(M2B-S)") (class "Default")
      (node (ref "M2") (pin "2") (pinfunction "S_2") (pintype "passive"))
      (node (ref "U$2") (pin "2A") (pinfunction "2A_2A") (pintype "output"))
    )
    (net (code "82") (name "Net-(M2C-S)") (class "Default")
      (node (ref "M2") (pin "3") (pinfunction "S_3") (pintype "passive"))
      (node (ref "U$2") (pin "1A") (pinfunction "1A_1A") (pintype "output"))
    )
    (net (code "83") (name "Net-(M2D-S)") (class "Default")
      (node (ref "M2") (pin "4") (pinfunction "S_4") (pintype "passive"))
      (node (ref "U$2") (pin "1B") (pinfunction "1B_1B") (pintype "output"))
    )
    (net (code "84") (name "Net-(M3A-S)") (class "Default")
      (node (ref "M3") (pin "1") (pinfunction "S_1") (pintype "passive"))
      (node (ref "U$3") (pin "2B") (pinfunction "2B_2B") (pintype "output"))
    )
    (net (code "85") (name "Net-(M3B-S)") (class "Default")
      (node (ref "M3") (pin "2") (pinfunction "S_2") (pintype "passive"))
      (node (ref "U$3") (pin "2A") (pinfunction "2A_2A") (pintype "output"))
    )
    (net (code "86") (name "Net-(M3C-S)") (class "Default")
      (node (ref "M3") (pin "3") (pinfunction "S_3") (pintype "passive"))
      (node (ref "U$3") (pin "1A") (pinfunction "1A_1A") (pintype "output"))
    )
    (net (code "87") (name "Net-(M3D-S)") (class "Default")
      (node (ref "M3") (pin "4") (pinfunction "S_4") (pintype "passive"))
      (node (ref "U$3") (pin "1B") (pinfunction "1B_1B") (pintype "output"))
    )
    (net (code "88") (name "Net-(M4AA-S)") (class "Default")
      (node (ref "M4A") (pin "1") (pinfunction "S_1") (pintype "passive"))
      (node (ref "U$4") (pin "2B") (pinfunction "2B_2B") (pintype "output"))
    )
    (net (code "89") (name "Net-(M4AB-S)") (class "Default")
      (node (ref "M4A") (pin "2") (pinfunction "S_2") (pintype "passive"))
      (node (ref "M4B") (pin "1") (pinfunction "S_1") (pintype "passive"))
    )
    (net (code "90") (name "Net-(M4AC-S)") (class "Default")
      (node (ref "M4A") (pin "3") (pinfunction "S_3") (pintype "passive"))
      (node (ref "M4B") (pin "4") (pinfunction "S_4") (pintype "passive"))
    )
    (net (code "91") (name "Net-(M4AD-S)") (class "Default")
      (node (ref "M4A") (pin "4") (pinfunction "S_4") (pintype "passive"))
      (node (ref "U$4") (pin "1B") (pinfunction "1B_1B") (pintype "output"))
    )
    (net (code "92") (name "Net-(M4BB-S)") (class "Default")
      (node (ref "M4B") (pin "2") (pinfunction "S_2") (pintype "passive"))
      (node (ref "U$4") (pin "2A") (pinfunction "2A_2A") (pintype "output"))
    )
    (net (code "93") (name "Net-(M4BC-S)") (class "Default")
      (node (ref "M4B") (pin "3") (pinfunction "S_3") (pintype "passive"))
      (node (ref "U$4") (pin "1A") (pinfunction "1A_1A") (pintype "output"))
    )
    (net (code "94") (name "Net-(Q1-PadG)") (class "Default")
      (node (ref "Q1") (pin "G") (pinfunction "G_G") (pintype "passive"))
      (node (ref "R1") (pin "2") (pinfunction "2_2") (pintype "passive"))
      (node (ref "R2") (pin "2") (pinfunction "2_2") (pintype "passive"))
    )
    (net (code "95") (name "Net-(Q2-PadG)") (class "Default")
      (node (ref "Q2") (pin "G") (pinfunction "G_G") (pintype "passive"))
      (node (ref "R3") (pin "2") (pinfunction "2_2") (pintype "passive"))
      (node (ref "R4") (pin "2") (pinfunction "2_2") (pintype "passive"))
    )
    (net (code "96") (name "Net-(Q3-PadG)") (class "Default")
      (node (ref "Q3") (pin "G") (pinfunction "G_G") (pintype "passive"))
      (node (ref "R23") (pin "2") (pinfunction "2_2") (pintype "passive"))
    )
    (net (code "97") (name "Net-(Q4-PadG)") (class "Default")
      (node (ref "Q4") (pin "G") (pinfunction "G_G") (pintype "passive"))
      (node (ref "R26") (pin "2") (pinfunction "2_2") (pintype "passive"))
    )
    (net (code "98") (name "Net-(Q5-PadG)") (class "Default")
      (node (ref "Q5") (pin "G") (pinfunction "G_G") (pintype "passive"))
      (node (ref "R29") (pin "2") (pinfunction "2_2") (pintype "passive"))
    )
    (net (code "99") (name "Net-(Q6-PadG)") (class "Default")
      (node (ref "Q6") (pin "G") (pinfunction "G_G") (pintype "passive"))
      (node (ref "R32") (pin "2") (pinfunction "2_2") (pintype "passive"))
    )
    (net (code "100") (name "Net-(R16-Pad1)") (class "Default")
      (node (ref "R16") (pin "1") (pinfunction "1_1") (pintype "passive"))
      (node (ref "TX") (pin "A") (pinfunction "A_A") (pintype "passive"))
    )
    (net (code "101") (name "Net-(R17-Pad1)") (class "Default")
      (node (ref "R17") (pin "1") (pinfunction "1_1") (pintype "passive"))
      (node (ref "RX") (pin "A") (pinfunction "A_A") (pintype "passive"))
    )
    (net (code "102") (name "unconnected-(IC3-(A8)PC0-Pad53)") (class "Default")
      (node (ref "IC3") (pin "53") (pinfunction "(A8)PC0_53") (pintype "bidirectional"))
    )
    (net (code "103") (name "unconnected-(IC3-(A9)PC1-Pad54)") (class "Default")
      (node (ref "IC3") (pin "54") (pinfunction "(A9)PC1_54") (pintype "bidirectional"))
    )
    (net (code "104") (name "unconnected-(IC3-(A10)PC2-Pad55)") (class "Default")
      (node (ref "IC3") (pin "55") (pinfunction "(A10)PC2_55") (pintype "bidirectional"))
    )
    (net (code "105") (name "unconnected-(IC3-(A11)PC3-Pad56)") (class "Default")
      (node (ref "IC3") (pin "56") (pinfunction "(A11)PC3_56") (pintype "bidirectional"))
    )
    (net (code "106") (name "unconnected-(IC3-(A12)PC4-Pad57)") (class "Default")
      (node (ref "IC3") (pin "57") (pinfunction "(A12)PC4_57") (pintype "bidirectional"))
    )
    (net (code "107") (name "unconnected-(IC3-(A13)PC5-Pad58)") (class "Default")
      (node (ref "IC3") (pin "58") (pinfunction "(A13)PC5_58") (pintype "bidirectional"))
    )
    (net (code "108") (name "unconnected-(IC3-(A14)PC6-Pad59)") (class "Default")
      (node (ref "IC3") (pin "59") (pinfunction "(A14)PC6_59") (pintype "bidirectional"))
    )
    (net (code "109") (name "unconnected-(IC3-(A15)PC7-Pad60)") (class "Default")
      (node (ref "IC3") (pin "60") (pinfunction "(A15)PC7_60") (pintype "bidirectional"))
    )
    (net (code "110") (name "unconnected-(IC3-(AD3)PA3-Pad75)") (class "Default")
      (node (ref "IC3") (pin "75") (pinfunction "(AD3)PA3_75") (pintype "bidirectional"))
    )
    (net (code "111") (name "unconnected-(IC3-(AD4)PA4-Pad74)") (class "Default")
      (node (ref "IC3") (pin "74") (pinfunction "(AD4)PA4_74") (pintype "bidirectional"))
    )
    (net (code "112") (name "unconnected-(IC3-(AD5)PA5-Pad73)") (class "Default")
      (node (ref "IC3") (pin "73") (pinfunction "(AD5)PA5_73") (pintype "bidirectional"))
    )
    (net (code "113") (name "unconnected-(IC3-(AD6)PA6-Pad72)") (class "Default")
      (node (ref "IC3") (pin "72") (pinfunction "(AD6)PA6_72") (pintype "bidirectional"))
    )
    (net (code "114") (name "unconnected-(IC3-(AD7)PA7-Pad71)") (class "Default")
      (node (ref "IC3") (pin "71") (pinfunction "(AD7)PA7_71") (pintype "bidirectional"))
    )
    (net (code "115") (name "unconnected-(IC3-(ALE)PG2-Pad70)") (class "Default")
      (node (ref "IC3") (pin "70") (pinfunction "(ALE)PG2_70") (pintype "bidirectional"))
    )
    (net (code "116") (name "unconnected-(IC3-(CLKO{slash}ICP3{slash}INT7)PE7-Pad9)") (class "Default")
      (node (ref "IC3") (pin "9") (pinfunction "(CLKO/ICP3/INT7)PE7_9") (pintype "bidirectional"))
    )
    (net (code "117") (name "unconnected-(IC3-(ICP1)PD4-Pad47)") (class "Default")
      (node (ref "IC3") (pin "47") (pinfunction "(ICP1)PD4_47") (pintype "bidirectional"))
    )
    (net (code "118") (name "unconnected-(IC3-(OC0A{slash}OC1C{slash}PCINT7)PB7-Pad26)") (class "Default")
      (node (ref "IC3") (pin "26") (pinfunction "(OC0A/OC1C/PCINT7)PB7_26") (pintype "bidirectional"))
    )
    (net (code "119") (name "unconnected-(IC3-(OC0B)PG5-Pad1)") (class "Default")
      (node (ref "IC3") (pin "1") (pinfunction "(OC0B)PG5_1") (pintype "bidirectional"))
    )
    (net (code "120") (name "unconnected-(IC3-(OC1A{slash}PCINT5)PB5-Pad24)") (class "Default")
      (node (ref "IC3") (pin "24") (pinfunction "(OC1A/PCINT5)PB5_24") (pintype "bidirectional"))
    )
    (net (code "121") (name "unconnected-(IC3-(OC1B{slash}PCINT6)PB6-Pad25)") (class "Default")
      (node (ref "IC3") (pin "25") (pinfunction "(OC1B/PCINT6)PB6_25") (pintype "bidirectional"))
    )
    (net (code "122") (name "unconnected-(IC3-(OC2A{slash}PCINT4)PB4-Pad23)") (class "Default")
      (node (ref "IC3") (pin "23") (pinfunction "(OC2A/PCINT4)PB4_23") (pintype "bidirectional"))
    )
    (net (code "123") (name "unconnected-(IC3-(OC3A{slash}AIN1)PE3-Pad5)") (class "Default")
      (node (ref "IC3") (pin "5") (pinfunction "(OC3A/AIN1)PE3_5") (pintype "bidirectional"))
    )
    (net (code "124") (name "unconnected-(IC3-(OC3B{slash}INT4)PE4-Pad6)") (class "Default")
      (node (ref "IC3") (pin "6") (pinfunction "(OC3B/INT4)PE4_6") (pintype "bidirectional"))
    )
    (net (code "125") (name "unconnected-(IC3-(OC3C{slash}INT5)PE5-Pad7)") (class "Default")
      (node (ref "IC3") (pin "7") (pinfunction "(OC3C/INT5)PE5_7") (pintype "bidirectional"))
    )
    (net (code "126") (name "unconnected-(IC3-(RD)PG1-Pad52)") (class "Default")
      (node (ref "IC3") (pin "52") (pinfunction "(RD)PG1_52") (pintype "bidirectional"))
    )
    (net (code "127") (name "unconnected-(IC3-(RXD1{slash}INT2)PD2-Pad45)") (class "Default")
      (node (ref "IC3") (pin "45") (pinfunction "(RXD1/INT2)PD2_45") (pintype "bidirectional"))
    )
    (net (code "128") (name "unconnected-(IC3-(SCL{slash}INT0)PD0-Pad43)") (class "Default")
      (node (ref "IC3") (pin "43") (pinfunction "(SCL/INT0)PD0_43") (pintype "bidirectional"))
    )
    (net (code "129") (name "unconnected-(IC3-(SDA{slash}INT1)PD1-Pad44)") (class "Default")
      (node (ref "IC3") (pin "44") (pinfunction "(SDA/INT1)PD1_44") (pintype "bidirectional"))
    )
    (net (code "130") (name "unconnected-(IC3-(T0)PD7-Pad50)") (class "Default")
      (node (ref "IC3") (pin "50") (pinfunction "(T0)PD7_50") (pintype "bidirectional"))
    )
    (net (code "131") (name "unconnected-(IC3-(T1)PD6-Pad49)") (class "Default")
      (node (ref "IC3") (pin "49") (pinfunction "(T1)PD6_49") (pintype "bidirectional"))
    )
    (net (code "132") (name "unconnected-(IC3-(T3{slash}INT6)PE6-Pad8)") (class "Default")
      (node (ref "IC3") (pin "8") (pinfunction "(T3/INT6)PE6_8") (pintype "bidirectional"))
    )
    (net (code "133") (name "unconnected-(IC3-(TOSC1)PG4-Pad29)") (class "Default")
      (node (ref "IC3") (pin "29") (pinfunction "(TOSC1)PG4_29") (pintype "bidirectional"))
    )
    (net (code "134") (name "unconnected-(IC3-(TOSC2)PG3-Pad28)") (class "Default")
      (node (ref "IC3") (pin "28") (pinfunction "(TOSC2)PG3_28") (pintype "bidirectional"))
    )
    (net (code "135") (name "unconnected-(IC3-(TXD1{slash}INT3)PD3-Pad46)") (class "Default")
      (node (ref "IC3") (pin "46") (pinfunction "(TXD1/INT3)PD3_46") (pintype "bidirectional"))
    )
    (net (code "136") (name "unconnected-(IC3-(WR)PG0-Pad51)") (class "Default")
      (node (ref "IC3") (pin "51") (pinfunction "(WR)PG0_51") (pintype "bidirectional"))
    )
    (net (code "137") (name "unconnected-(IC3-(XCK0{slash}AIN0)PE2-Pad4)") (class "Default")
      (node (ref "IC3") (pin "4") (pinfunction "(XCK0/AIN0)PE2_4") (pintype "bidirectional"))
    )
    (net (code "138") (name "unconnected-(IC3-(XCK1)PD5-Pad48)") (class "Default")
      (node (ref "IC3") (pin "48") (pinfunction "(XCK1)PD5_48") (pintype "bidirectional"))
    )
    (net (code "139") (name "unconnected-(IC3-PH0(RXD2)-Pad12)") (class "Default")
      (node (ref "IC3") (pin "12") (pinfunction "PH0(RXD2)_12") (pintype "bidirectional"))
    )
    (net (code "140") (name "unconnected-(IC3-PH1(TXD2)-Pad13)") (class "Default")
      (node (ref "IC3") (pin "13") (pinfunction "PH1(TXD2)_13") (pintype "bidirectional"))
    )
    (net (code "141") (name "unconnected-(IC3-PH2(XCK2)-Pad14)") (class "Default")
      (node (ref "IC3") (pin "14") (pinfunction "PH2(XCK2)_14") (pintype "bidirectional"))
    )
    (net (code "142") (name "unconnected-(IC3-PH3(OC4A)-Pad15)") (class "Default")
      (node (ref "IC3") (pin "15") (pinfunction "PH3(OC4A)_15") (pintype "bidirectional"))
    )
    (net (code "143") (name "unconnected-(IC3-PH4(OC4B)-Pad16)") (class "Default")
      (node (ref "IC3") (pin "16") (pinfunction "PH4(OC4B)_16") (pintype "bidirectional"))
    )
    (net (code "144") (name "unconnected-(IC3-PH5(OC4C)-Pad17)") (class "Default")
      (node (ref "IC3") (pin "17") (pinfunction "PH5(OC4C)_17") (pintype "bidirectional"))
    )
    (net (code "145") (name "unconnected-(IC3-PH6(OC2B)-Pad18)") (class "Default")
      (node (ref "IC3") (pin "18") (pinfunction "PH6(OC2B)_18") (pintype "bidirectional"))
    )
    (net (code "146") (name "unconnected-(IC3-PH7(T4)-Pad27)") (class "Default")
      (node (ref "IC3") (pin "27") (pinfunction "PH7(T4)_27") (pintype "bidirectional"))
    )
    (net (code "147") (name "unconnected-(IC3-PJ0(RXD3{slash}PCINT9)-Pad63)") (class "Default")
      (node (ref "IC3") (pin "63") (pinfunction "PJ0(RXD3/PCINT9)_63") (pintype "bidirectional"))
    )
    (net (code "148") (name "unconnected-(IC3-PJ1(TXD3{slash}PCINT10)-Pad64)") (class "Default")
      (node (ref "IC3") (pin "64") (pinfunction "PJ1(TXD3/PCINT10)_64") (pintype "bidirectional"))
    )
    (net (code "149") (name "unconnected-(IC3-PJ2(XCK3{slash}PCINT11)-Pad65)") (class "Default")
      (node (ref "IC3") (pin "65") (pinfunction "PJ2(XCK3/PCINT11)_65") (pintype "bidirectional"))
    )
    (net (code "150") (name "unconnected-(IC3-PJ3(PCINT12)-Pad66)") (class "Default")
      (node (ref "IC3") (pin "66") (pinfunction "PJ3(PCINT12)_66") (pintype "bidirectional"))
    )
    (net (code "151") (name "unconnected-(IC3-PJ4(PCINT13)-Pad67)") (class "Default")
      (node (ref "IC3") (pin "67") (pinfunction "PJ4(PCINT13)_67") (pintype "bidirectional"))
    )
    (net (code "152") (name "unconnected-(IC3-PJ5(PCINT14)-Pad68)") (class "Default")
      (node (ref "IC3") (pin "68") (pinfunction "PJ5(PCINT14)_68") (pintype "bidirectional"))
    )
    (net (code "153") (name "unconnected-(IC3-PJ6(PCINT15)-Pad69)") (class "Default")
      (node (ref "IC3") (pin "69") (pinfunction "PJ6(PCINT15)_69") (pintype "bidirectional"))
    )
    (net (code "154") (name "unconnected-(IC3-PJ7-Pad79)") (class "Default")
      (node (ref "IC3") (pin "79") (pinfunction "PJ7_79") (pintype "bidirectional"))
    )
    (net (code "155") (name "unconnected-(IC3-PL0(ICP4)-Pad35)") (class "Default")
      (node (ref "IC3") (pin "35") (pinfunction "PL0(ICP4)_35") (pintype "bidirectional"))
    )
    (net (code "156") (name "unconnected-(IC3-PL1(ICP5)-Pad36)") (class "Default")
      (node (ref "IC3") (pin "36") (pinfunction "PL1(ICP5)_36") (pintype "bidirectional"))
    )
    (net (code "157") (name "unconnected-(IC3-PL2(T5)-Pad37)") (class "Default")
      (node (ref "IC3") (pin "37") (pinfunction "PL2(T5)_37") (pintype "bidirectional"))
    )
    (net (code "158") (name "unconnected-(IC3-PL3(OC5A)-Pad38)") (class "Default")
      (node (ref "IC3") (pin "38") (pinfunction "PL3(OC5A)_38") (pintype "bidirectional"))
    )
    (net (code "159") (name "unconnected-(IC3-PL6-Pad41)") (class "Default")
      (node (ref "IC3") (pin "41") (pinfunction "PL6_41") (pintype "bidirectional"))
    )
    (net (code "160") (name "unconnected-(IC3-PL7-Pad42)") (class "Default")
      (node (ref "IC3") (pin "42") (pinfunction "PL7_42") (pintype "bidirectional"))
    )
    (net (code "161") (name "unconnected-(IC4-(AIN0{slash}INT1)PD1-Pad7)") (class "Default")
      (node (ref "IC4") (pin "7") (pinfunction "(AIN0/INT1)PD1_7") (pintype "bidirectional"))
    )
    (net (code "162") (name "unconnected-(IC4-(AIN2{slash}PCINT11)PC2-Pad5)") (class "Default")
      (node (ref "IC4") (pin "5") (pinfunction "(AIN2/PCINT11)PC2_5") (pintype "bidirectional"))
    )
    (net (code "163") (name "unconnected-(IC4-(INT4{slash}ICP1{slash}CLK0)PC7-Pad22)") (class "Default")
      (node (ref "IC4") (pin "22") (pinfunction "(INT4/ICP1/CLK0)PC7_22") (pintype "bidirectional"))
    )
    (net (code "164") (name "unconnected-(IC4-(OC0B{slash}INT0)PD0-Pad6)") (class "Default")
      (node (ref "IC4") (pin "6") (pinfunction "(OC0B/INT0)PD0_6") (pintype "bidirectional"))
    )
    (net (code "165") (name "unconnected-(IC4-(OC1A{slash}PCINT8)PC6-Pad23)") (class "Default")
      (node (ref "IC4") (pin "23") (pinfunction "(OC1A/PCINT8)PC6_23") (pintype "bidirectional"))
    )
    (net (code "166") (name "unconnected-(IC4-(PCINT9{slash}OC1B)PC5-Pad25)") (class "Default")
      (node (ref "IC4") (pin "25") (pinfunction "(PCINT9/OC1B)PC5_25") (pintype "bidirectional"))
    )
    (net (code "167") (name "unconnected-(IC4-(PCINT10)PC4-Pad26)") (class "Default")
      (node (ref "IC4") (pin "26") (pinfunction "(PCINT10)PC4_26") (pintype "bidirectional"))
    )
    (net (code "168") (name "unconnected-(IC4-(RTS{slash}AIN5{slash}INT6)PD6-Pad12)") (class "Default")
      (node (ref "IC4") (pin "12") (pinfunction "(RTS/AIN5/INT6)PD6_12") (pintype "bidirectional"))
    )
    (net (code "169") (name "unconnected-(IC4-(SS{slash}PCINT0)PB0-Pad14)") (class "Default")
      (node (ref "IC4") (pin "14") (pinfunction "(SS/PCINT0)PB0_14") (pintype "bidirectional"))
    )
  )
)
